# Power_Management.net
KiCad netlist of a schematic drawn in Altium Designer
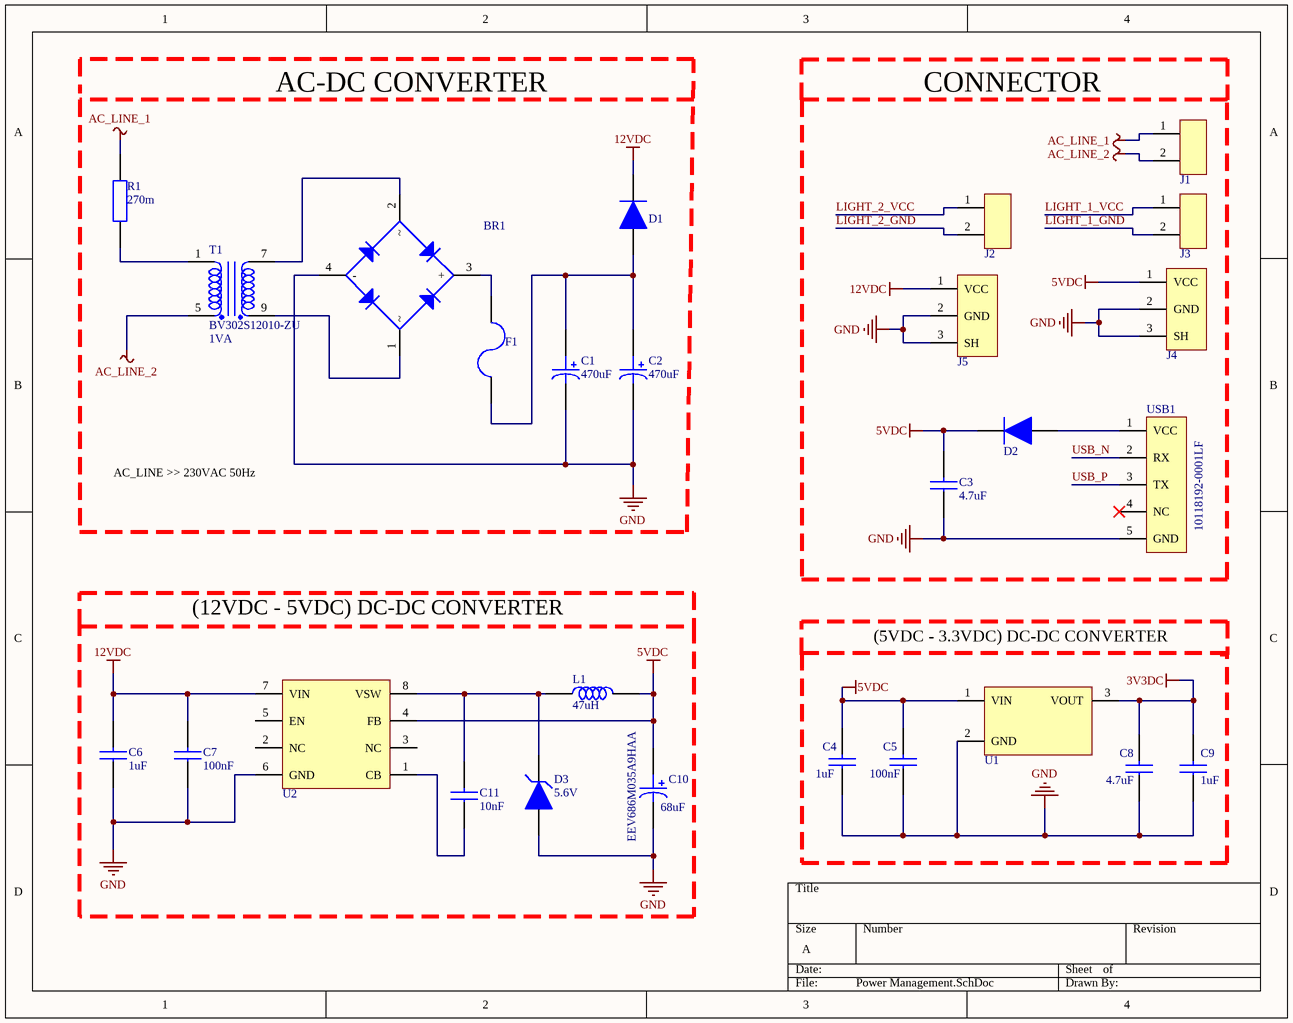
[diagram p0: Power Management.SchDoc]

(export (version "E")
  (design (tool "Eeschema 10.0.6"))
  (components
    (comp (ref "BR1")
      (value "DB105STR")
      (footprint "DB105STR")
      (description "Bridge Diode AC-DC")
      (fields (field (name "MANUFACTURER") "Sangdest Microelectronics") (field (name "DESIGNED BY") "BERK"))
      (libsource (lib "UDEMY_Library") (part "DB105STR"))
    )
    (comp (ref "C1")
      (value "ESH477M050AH4AA")
      (footprint "CAP_RADIAL_D10_P5")
      (description "CAP ALU ELEC 470uF 50V RADIAL")
      (fields
        (field (name "MANUFACTURER") "KEMET")
        (field (name "TOLERANCE") "20%")
        (field (name "CAPACITANCE") "470uF")
        (field (name "DESIGNED BY") "BERK")
      )
      (libsource (lib "UDEMY_Library") (part "CAP ALU ELEC 470uF 50V"))
    )
    (comp (ref "C2")
      (value "ESH477M050AH4AA")
      (footprint "CAP_RADIAL_D10_P5")
      (description "CAP ALU ELEC 470uF 50V RADIAL")
      (fields
        (field (name "MANUFACTURER") "KEMET")
        (field (name "TOLERANCE") "20%")
        (field (name "CAPACITANCE") "470uF")
        (field (name "DESIGNED BY") "BERK")
      )
      (libsource (lib "UDEMY_Library") (part "CAP ALU ELEC 470uF 50V"))
    )
    (comp (ref "C3")
      (value "CL21A475KAQNNNE")
      (footprint "CAP_0805")
      (description "CAP CER 4.7uF %10 0805")
      (fields
        (field (name "MANUFACTURER") "Samsung")
        (field (name "TOLERANCE") "10%")
        (field (name "CAPACITANCE") "4.7uF")
        (field (name "DESIGNED BY") "BERK")
      )
      (libsource (lib "UDEMY_Library") (part "CAP CER 4.7uF 0805"))
    )
    (comp (ref "C4")
      (value "CL21B105KBFNNNE")
      (footprint "CAP_0805")
      (description "CAP CER 1uF %10 0805")
      (fields
        (field (name "MANUFACTURER") "Samsung")
        (field (name "TOLERANCE") "10%")
        (field (name "CAPACITANCE") "1uF")
        (field (name "DESIGNED BY") "BERK")
      )
      (libsource (lib "UDEMY_Library") (part "CAP CER 1uF 0805"))
    )
    (comp (ref "C5")
      (value "CL21B104KBCNNNC")
      (footprint "CAP_0805")
      (description "CAP CER 100nF %10 0805")
      (fields
        (field (name "MANUFACTURER") "Samsung")
        (field (name "TOLERANCE") "10%")
        (field (name "CAPACITANCE") "100nF")
        (field (name "DESIGNED BY") "BERK")
      )
      (libsource (lib "UDEMY_Library") (part "CAP CER 100nF 0805"))
    )
    (comp (ref "C6")
      (value "CL21B105KBFNNNE")
      (footprint "CAP_0805")
      (description "CAP CER 1uF %10 0805")
      (fields
        (field (name "MANUFACTURER") "Samsung")
        (field (name "TOLERANCE") "10%")
        (field (name "CAPACITANCE") "1uF")
        (field (name "DESIGNED BY") "BERK")
      )
      (libsource (lib "UDEMY_Library") (part "CAP CER 1uF 0805"))
    )
    (comp (ref "C7")
      (value "CL21B104KBCNNNC")
      (footprint "CAP_0805")
      (description "CAP CER 100nF %10 0805")
      (fields
        (field (name "MANUFACTURER") "Samsung")
        (field (name "TOLERANCE") "10%")
        (field (name "CAPACITANCE") "100nF")
        (field (name "DESIGNED BY") "BERK")
      )
      (libsource (lib "UDEMY_Library") (part "CAP CER 100nF 0805"))
    )
    (comp (ref "C8")
      (value "CL21A475KAQNNNE")
      (footprint "CAP_0805")
      (description "CAP CER 4.7uF %10 0805")
      (fields
        (field (name "MANUFACTURER") "Samsung")
        (field (name "TOLERANCE") "10%")
        (field (name "CAPACITANCE") "4.7uF")
        (field (name "DESIGNED BY") "BERK")
      )
      (libsource (lib "UDEMY_Library") (part "CAP CER 4.7uF 0805"))
    )
    (comp (ref "C9")
      (value "CL21B105KBFNNNE")
      (footprint "CAP_0805")
      (description "CAP CER 1uF %10 0805")
      (fields
        (field (name "MANUFACTURER") "Samsung")
        (field (name "TOLERANCE") "10%")
        (field (name "CAPACITANCE") "1uF")
        (field (name "DESIGNED BY") "BERK")
      )
      (libsource (lib "UDEMY_Library") (part "CAP CER 1uF 0805"))
    )
    (comp (ref "C10")
      (value "EEV686M035A9HAA")
      (footprint "CAP_EEVseries")
      (description "Cap Aluminum Lytic 68uF 35V 20% (6.3 X 7.7mm) SMD 280mA 2000h 105C T/R")
      (fields
        (field (name "MANUFACTURER") "KEMET")
        (field (name "TOLERANCE") "20%")
        (field (name "CAPACITANCE") "68uF")
      )
      (libsource (lib "UDEMY_Library") (part "CAP ALU 68uF"))
    )
    (comp (ref "C11")
      (value "0603B103K160CT")
      (footprint "CAP_0603")
      (description "CAP CER 10nF %10 0603")
      (fields
        (field (name "MANUFACTURER") "Walsin Technologies")
        (field (name "TOLERANCE") "10%")
        (field (name "CAPACITANCE") "10nF")
        (field (name "DESIGNED BY") "BERK")
      )
      (libsource (lib "UDEMY_Library") (part "CAP CER 10nF 0603"))
    )
    (comp (ref "D1")
      (value "1N4148WS")
      (footprint "SOD323F")
      (description "Diode, Single, 75 V, 150 mA, 1 V, 4 ns")
      (fields
        (field (name "MANUFACTURER") "ON Semiconductor / Fairchild")
        (field (name "DESIGNED BY") "BERK")
      )
      (libsource (lib "UDEMY_Library") (part "1N4148WS"))
    )
    (comp (ref "D2")
      (value "1N4148WS")
      (footprint "SOD323F")
      (description "Diode, Single, 75 V, 150 mA, 1 V, 4 ns")
      (fields
        (field (name "MANUFACTURER") "ON Semiconductor / Fairchild")
        (field (name "DESIGNED BY") "BERK")
      )
      (libsource (lib "UDEMY_Library") (part "1N4148WS"))
    )
    (comp (ref "D3")
      (value "1SMB5919BT3G")
      (footprint "SMB")
      (description "Diode Zener Single 5.6V 5% 3W 2-Pin SMB T/R")
      (fields
        (field (name "MANUFACTURER") "ON Semiconductor")
        (field (name "TOLERANCE") "5%")
        (field (name "WORKING VOLTAGE") "5.6V")
        (field (name "DESIGNED BY") "BERK")
      )
      (libsource (lib "UDEMY_Library") (part "1SMB5919BT3G"))
    )
    (comp (ref "F1")
      (value "3413.0216.22")
      (footprint "3413.0216.22")
      (description "FUSE BRD MNT 1A 32VAC 63VDC 1206")
      (fields (field (name "MANUFACTURER") "Schurter") (field (name "DESIGNED BY") "BERK"))
      (libsource (lib "UDEMY_Library") (part "FUSE 3413.0216.22"))
    )
    (comp (ref "J1")
      (value "TBP01R1-508-02BE")
      (footprint "TBP01R1-508")
      (description "Conn Shrouded Header HDR 2 POS 5.08mm Solder RA Side Entry Thru-Hole Bag")
      (fields (field (name "MANUFACTURER") "CUI") (field (name "DESIGNED BY") "BERK"))
      (libsource (lib "UDEMY_Library") (part "TBP01R1-508-02BE"))
    )
    (comp (ref "J2")
      (value "TBP01R1-508-02BE")
      (footprint "TBP01R1-508")
      (description "Conn Shrouded Header HDR 2 POS 5.08mm Solder RA Side Entry Thru-Hole Bag")
      (fields (field (name "MANUFACTURER") "CUI") (field (name "DESIGNED BY") "BERK"))
      (libsource (lib "UDEMY_Library") (part "TBP01R1-508-02BE"))
    )
    (comp (ref "J3")
      (value "TBP01R1-508-02BE")
      (footprint "TBP01R1-508")
      (description "Conn Shrouded Header HDR 2 POS 5.08mm Solder RA Side Entry Thru-Hole Bag")
      (fields (field (name "MANUFACTURER") "CUI") (field (name "DESIGNED BY") "BERK"))
      (libsource (lib "UDEMY_Library") (part "TBP01R1-508-02BE"))
    )
    (comp (ref "J4")
      (value "PJ-037AH-SMT-TR")
      (footprint "JACK")
      (description "DC Power Connectors Power Jacks")
      (fields (field (name "MANUFACTURER") "CUI") (field (name "DESIGNED BY") "BERK"))
      (libsource (lib "UDEMY_Library") (part "PJ-037AH-SMT-TR"))
    )
    (comp (ref "J5")
      (value "PJ-037AH-SMT-TR")
      (footprint "JACK")
      (description "DC Power Connectors Power Jacks")
      (fields (field (name "MANUFACTURER") "CUI") (field (name "DESIGNED BY") "BERK"))
      (libsource (lib "UDEMY_Library") (part "PJ-037AH-SMT-TR"))
    )
    (comp (ref "L1")
      (value "78438335470")
      (footprint "IND_1212")
      (description "FIXED IND 47UH 390MA 2.3 OHM SMD")
      (fields
        (field (name "MANUFACTURER") "Wurth Electronics")
        (field (name "TOLERANCE") "30%")
        (field (name "INDUCTANCE") "47uH")
        (field (name "DESIGNED BY") "BERK")
      )
      (libsource (lib "UDEMY_Library") (part "IND 47uH"))
    )
    (comp (ref "R1")
      (value "5WD27")
      (footprint "RES_AXIAL_W")
      (description "Resistor 5 Watt Cermet Wirewound Flameproof .27 Ohm 5% Axial Lead")
      (fields
        (field (name "MANUFACTURER") "NTE Electronics")
        (field (name "TOLERANCE") "5%")
        (field (name "RESISTANCE") "270m")
        (field (name "DESIGNED BY") "BERK")
      )
      (libsource (lib "UDEMY_Library") (part "5WD27"))
    )
    (comp (ref "T1")
      (value "BV302S12010-ZU")
      (footprint "BV302S")
      (description "230-12 Transformer 1VA")
      (fields
        (field (name "MANUFACTURER") "Zettler Magnetics")
        (field (name "RATED POWER") "1VA")
        (field (name "DESIGNED BY") "BERK")
      )
      (libsource (lib "UDEMY_Library") (part "BV302S12010-ZU"))
    )
    (comp (ref "U1")
      (value "AP7361-33E-13")
      (footprint "SOT223")
      (description "LDO Regulator Pos 3.3V 1A 4-Pin(3+Tab) SOT-223 T/R")
      (fields (field (name "MANUFACTURER") "Diodes") (field (name "DESIGNED BY") "BERK"))
      (libsource (lib "UDEMY_Library") (part "AP7361-33E-13"))
    )
    (comp (ref "U2")
      (value "LM2675MX-12/NOPB")
      (footprint "SOIC8")
      (description "Switching Voltage Regulators Pwr Cnvtr Hi Eff 1A SD Vtg Reg")
      (fields (field (name "MANUFACTURER") "TI National Semiconductor") (field (name "DESIGNED BY") "BERK"))
      (libsource (lib "UDEMY_Library") (part "LM2675MX-12/NOPB"))
    )
    (comp (ref "USB1")
      (value "10118192-0001LF")
      (footprint "MICRO_B_USB")
      (description "CONN RCPT USB2.0 MICRO B SMD R/A")
      (fields (field (name "MANUFACTURER") "Amphenol FCI") (field (name "DESIGNED BY") "BERK"))
      (libsource (lib "UDEMY_Library") (part "Micro B USB Connector"))
    )
  )
  (nets
    (net (code "1") (name "/LIGHT_1_GND") (class "Default")
      (node (ref "J3") (pin "2") (pinfunction "2_2") (pintype "power_in"))
    )
    (net (code "2") (name "/LIGHT_1_VCC") (class "Default")
      (node (ref "J3") (pin "1") (pinfunction "1_1") (pintype "power_in"))
    )
    (net (code "3") (name "/LIGHT_2_GND") (class "Default")
      (node (ref "J2") (pin "2") (pinfunction "2_2") (pintype "power_in"))
    )
    (net (code "4") (name "/LIGHT_2_VCC") (class "Default")
      (node (ref "J2") (pin "1") (pinfunction "1_1") (pintype "power_in"))
    )
    (net (code "5") (name "/USB_N") (class "Default")
      (node (ref "USB1") (pin "2") (pinfunction "RX_2") (pintype "power_in"))
    )
    (net (code "6") (name "/USB_P") (class "Default")
      (node (ref "USB1") (pin "3") (pinfunction "TX_3") (pintype "power_in"))
    )
    (net (code "7") (name "3V3DC") (class "Default")
      (node (ref "C8") (pin "2") (pinfunction "2_2") (pintype "passive"))
      (node (ref "C9") (pin "2") (pinfunction "2_2") (pintype "passive"))
      (node (ref "U1") (pin "3") (pinfunction "VOUT_3") (pintype "passive"))
    )
    (net (code "8") (name "5VDC") (class "Default")
      (node (ref "C10") (pin "1") (pinfunction "1_1") (pintype "passive"))
      (node (ref "C3") (pin "2") (pinfunction "2_2") (pintype "passive"))
      (node (ref "C4") (pin "2") (pinfunction "2_2") (pintype "passive"))
      (node (ref "C5") (pin "2") (pinfunction "2_2") (pintype "passive"))
      (node (ref "D2") (pin "1") (pinfunction "1_1") (pintype "power_in"))
      (node (ref "J4") (pin "1") (pinfunction "VCC_1") (pintype "power_in"))
      (node (ref "L1") (pin "2") (pinfunction "2_2") (pintype "passive"))
      (node (ref "U1") (pin "1") (pinfunction "VIN_1") (pintype "passive"))
      (node (ref "U2") (pin "4") (pinfunction "FB_4") (pintype "passive"))
    )
    (net (code "9") (name "12VDC") (class "Default")
      (node (ref "C6") (pin "2") (pinfunction "2_2") (pintype "passive"))
      (node (ref "C7") (pin "2") (pinfunction "2_2") (pintype "passive"))
      (node (ref "D1") (pin "1") (pinfunction "1_1") (pintype "power_in"))
      (node (ref "J5") (pin "1") (pinfunction "VCC_1") (pintype "power_in"))
      (node (ref "U2") (pin "7") (pinfunction "VIN_7") (pintype "passive"))
    )
    (net (code "10") (name "AC_LINE_1") (class "Default")
      (node (ref "J1") (pin "1") (pinfunction "1_1") (pintype "power_in"))
      (node (ref "R1") (pin "1") (pinfunction "1_1") (pintype "passive"))
    )
    (net (code "11") (name "AC_LINE_2") (class "Default")
      (node (ref "J1") (pin "2") (pinfunction "2_2") (pintype "power_in"))
      (node (ref "T1") (pin "5") (pinfunction "5_5") (pintype "passive"))
    )
    (net (code "12") (name "GND") (class "Default")
      (node (ref "BR1") (pin "4") (pinfunction "-_4") (pintype "passive"))
      (node (ref "C1") (pin "2") (pinfunction "2_2") (pintype "passive"))
      (node (ref "C10") (pin "2") (pinfunction "2_2") (pintype "passive"))
      (node (ref "C2") (pin "2") (pinfunction "2_2") (pintype "passive"))
      (node (ref "C3") (pin "1") (pinfunction "1_1") (pintype "passive"))
      (node (ref "C4") (pin "1") (pinfunction "1_1") (pintype "passive"))
      (node (ref "C5") (pin "1") (pinfunction "1_1") (pintype "passive"))
      (node (ref "C6") (pin "1") (pinfunction "1_1") (pintype "passive"))
      (node (ref "C7") (pin "1") (pinfunction "1_1") (pintype "passive"))
      (node (ref "C8") (pin "1") (pinfunction "1_1") (pintype "passive"))
      (node (ref "C9") (pin "1") (pinfunction "1_1") (pintype "passive"))
      (node (ref "D3") (pin "A") (pinfunction "A_A") (pintype "passive"))
      (node (ref "J4") (pin "2") (pinfunction "GND_2") (pintype "power_in"))
      (node (ref "J4") (pin "3") (pinfunction "SH_3") (pintype "power_in"))
      (node (ref "J5") (pin "2") (pinfunction "GND_2") (pintype "power_in"))
      (node (ref "J5") (pin "3") (pinfunction "SH_3") (pintype "power_in"))
      (node (ref "U1") (pin "2") (pinfunction "GND_2") (pintype "passive"))
      (node (ref "U2") (pin "6") (pinfunction "GND_6") (pintype "passive"))
      (node (ref "USB1") (pin "5") (pinfunction "GND_5") (pintype "power_in"))
    )
    (net (code "13") (name "Net-(BR1-+)") (class "Default")
      (node (ref "BR1") (pin "3") (pinfunction "+_3") (pintype "passive"))
      (node (ref "F1") (pin "1") (pinfunction "1_1") (pintype "passive"))
    )
    (net (code "14") (name "Net-(BR1-~-Pad1)") (class "Default")
      (node (ref "BR1") (pin "1") (pinfunction "~_1") (pintype "passive"))
      (node (ref "T1") (pin "9") (pinfunction "9_9") (pintype "passive"))
    )
    (net (code "15") (name "Net-(BR1-~-Pad2)") (class "Default")
      (node (ref "BR1") (pin "2") (pinfunction "~_2") (pintype "passive"))
      (node (ref "T1") (pin "7") (pinfunction "7_7") (pintype "passive"))
    )
    (net (code "16") (name "Net-(C1-Pad1)") (class "Default")
      (node (ref "C1") (pin "1") (pinfunction "1_1") (pintype "passive"))
      (node (ref "C2") (pin "1") (pinfunction "1_1") (pintype "passive"))
      (node (ref "D1") (pin "2") (pinfunction "2_2") (pintype "power_in"))
      (node (ref "F1") (pin "2") (pinfunction "2_2") (pintype "passive"))
    )
    (net (code "17") (name "Net-(R1-Pad2)") (class "Default")
      (node (ref "R1") (pin "2") (pinfunction "2_2") (pintype "passive"))
      (node (ref "T1") (pin "1") (pinfunction "1_1") (pintype "passive"))
    )
    (net (code "18") (name "Net-(U2-CB)") (class "Default")
      (node (ref "C11") (pin "1") (pinfunction "1_1") (pintype "passive"))
      (node (ref "U2") (pin "1") (pinfunction "CB_1") (pintype "passive"))
    )
    (net (code "19") (name "Net-(U2-VSW)") (class "Default")
      (node (ref "C11") (pin "2") (pinfunction "2_2") (pintype "passive"))
      (node (ref "D3") (pin "C") (pinfunction "C_C") (pintype "passive"))
      (node (ref "L1") (pin "1") (pinfunction "1_1") (pintype "passive"))
      (node (ref "U2") (pin "8") (pinfunction "VSW_8") (pintype "passive"))
    )
    (net (code "20") (name "Net-(USB1-VCC)") (class "Default")
      (node (ref "D2") (pin "2") (pinfunction "2_2") (pintype "power_in"))
      (node (ref "USB1") (pin "1") (pinfunction "VCC_1") (pintype "power_in"))
    )
    (net (code "21") (name "unconnected-(U2-EN-Pad5)") (class "Default")
      (node (ref "U2") (pin "5") (pinfunction "EN_5") (pintype "passive"))
    )
    (net (code "22") (name "unconnected-(U2-NC-Pad2)") (class "Default")
      (node (ref "U2") (pin "2") (pinfunction "NC_2") (pintype "passive"))
    )
    (net (code "23") (name "unconnected-(U2-NC-Pad3)") (class "Default")
      (node (ref "U2") (pin "3") (pinfunction "NC_3") (pintype "passive"))
    )
    (net (code "24") (name "unconnected-(USB1-NC-Pad4)") (class "Default")
      (node (ref "USB1") (pin "4") (pinfunction "NC_4") (pintype "power_in+no_connect"))
    )
  )
)
